# AdaptadorAcceso.net
KiCad netlist of a schematic drawn in EAGLE
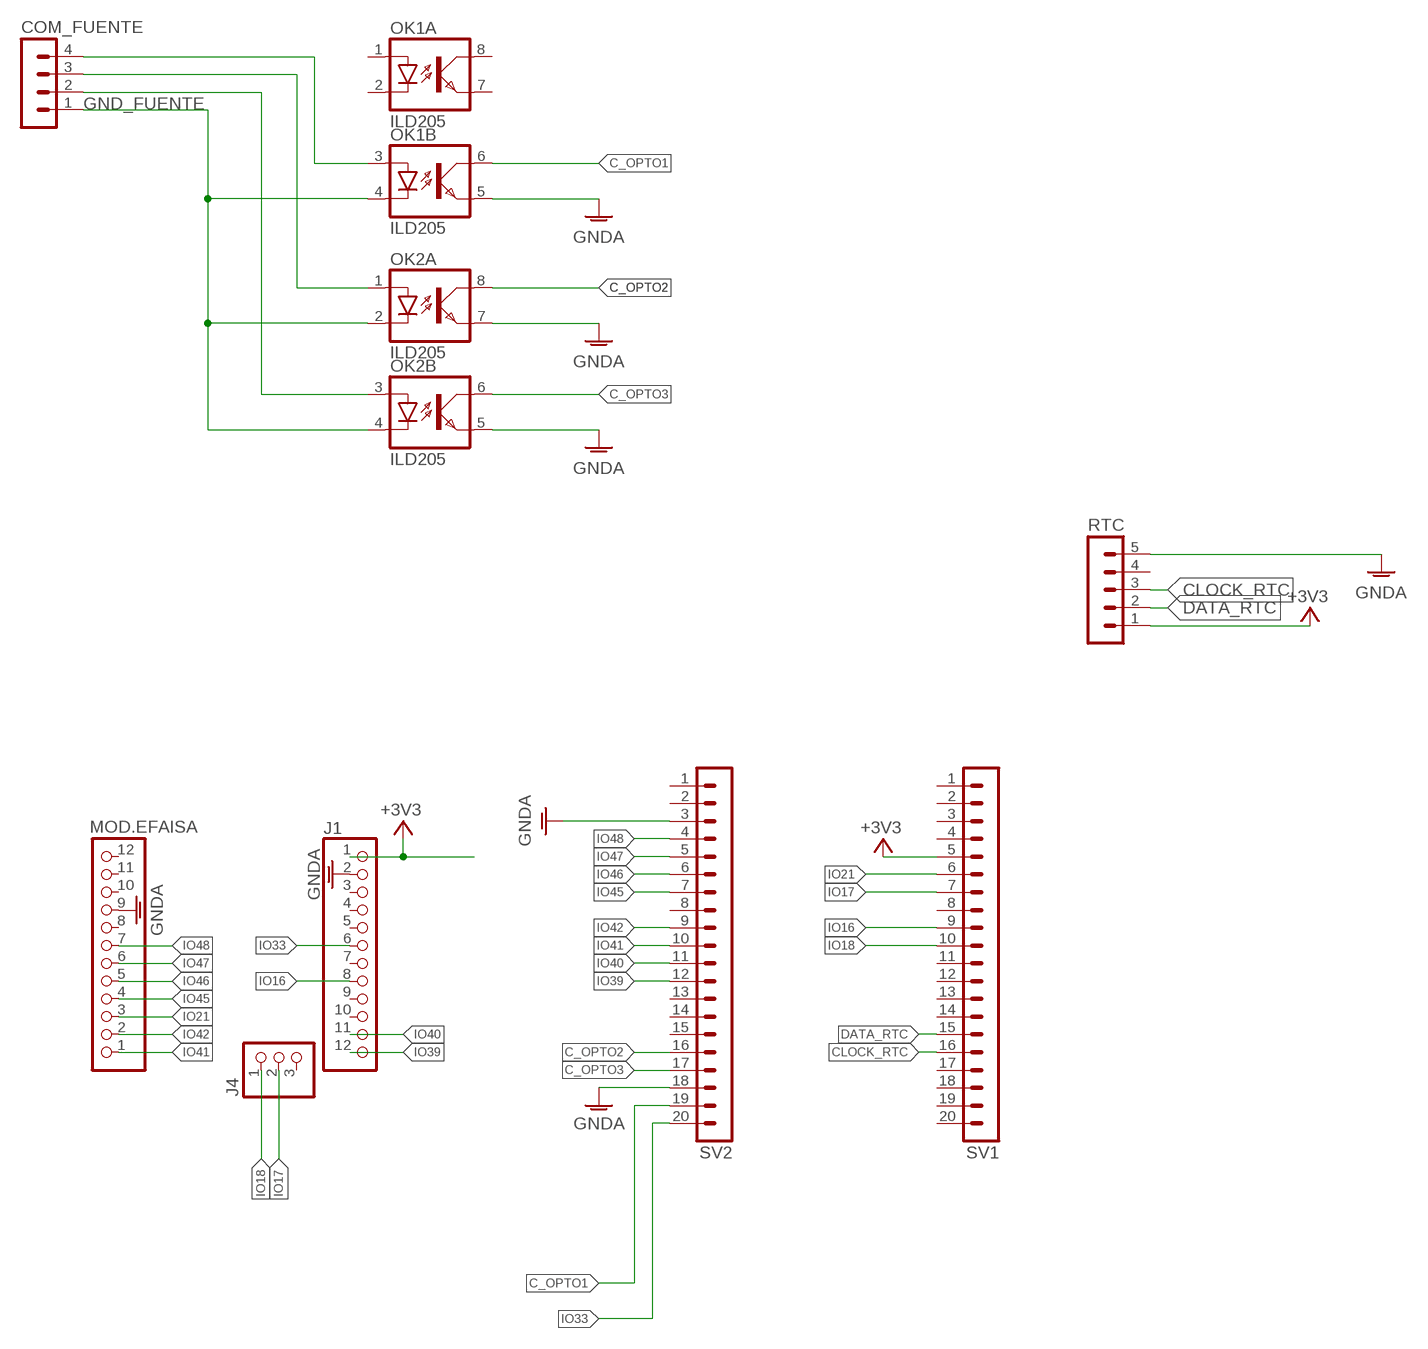
[diagram p0: schematic, sheet 1]

(export (version "E")
  (design (tool "Eeschema 10.0.6"))
  (components
    (comp (ref "COM_FUENTE")
      (value "MA04-1")
      (footprint "eagle-import:MA04-1")
      (libsource (lib "eagle-import") (part "MA04-1"))
    )
    (comp (ref "J1")
      (value "PINHD-1X12")
      (footprint "eagle-import:1X12")
      (libsource (lib "eagle-import") (part "PINHD-1X12"))
    )
    (comp (ref "J4")
      (value "PINHD-1X3")
      (footprint "eagle-import:1X03")
      (libsource (lib "eagle-import") (part "PINHD-1X3"))
    )
    (comp (ref "MOD.EFAISA")
      (value "PINHD-1X12")
      (footprint "eagle-import:1X12")
      (libsource (lib "eagle-import") (part "PINHD-1X12"))
    )
    (comp (ref "OK1")
      (value "ILD205")
      (footprint "eagle-import:SOIC08")
      (fields (field (name "MF") "VISHAY/TELEFUNKEN") (field (name "MPN") "ILD205T"))
      (libsource (lib "eagle-import") (part "ILD205"))
    )
    (comp (ref "OK2")
      (value "ILD205")
      (footprint "eagle-import:SOIC08")
      (fields (field (name "MF") "VISHAY/TELEFUNKEN") (field (name "MPN") "ILD205T"))
      (libsource (lib "eagle-import") (part "ILD205"))
    )
    (comp (ref "RTC")
      (value "MA05-1")
      (footprint "eagle-import:MA05-1")
      (libsource (lib "eagle-import") (part "MA05-1"))
    )
    (comp (ref "SV1")
      (value "MA20-1L")
      (footprint "eagle-import:MA20-1L")
      (libsource (lib "eagle-import") (part "MA20-1L"))
    )
    (comp (ref "SV2")
      (value "MA20-1L")
      (footprint "eagle-import:MA20-1L")
      (libsource (lib "eagle-import") (part "MA20-1L"))
    )
  )
  (nets
    (net (code "1") (name "+3V3") (class "Default")
      (node (ref "J1") (pin "1") (pinfunction "1_1") (pintype "passive"))
      (node (ref "RTC") (pin "1") (pinfunction "1_1") (pintype "passive"))
      (node (ref "SV1") (pin "5") (pinfunction "5_5") (pintype "passive"))
    )
    (net (code "2") (name "/GND_FUENTE") (class "Default")
      (node (ref "COM_FUENTE") (pin "1") (pinfunction "1_1") (pintype "passive"))
      (node (ref "OK1") (pin "4") (pinfunction "C_4") (pintype "passive"))
      (node (ref "OK2") (pin "2") (pinfunction "C_2") (pintype "passive"))
      (node (ref "OK2") (pin "4") (pinfunction "C_4") (pintype "passive"))
    )
    (net (code "3") (name "CLOCK_RTC") (class "Default")
      (node (ref "RTC") (pin "3") (pinfunction "3_3") (pintype "passive"))
      (node (ref "SV1") (pin "16") (pinfunction "16_16") (pintype "passive"))
    )
    (net (code "4") (name "C_OPTO1") (class "Default")
      (node (ref "OK1") (pin "6") (pinfunction "COL_6") (pintype "passive"))
      (node (ref "SV2") (pin "19") (pinfunction "19_19") (pintype "passive"))
    )
    (net (code "5") (name "C_OPTO2") (class "Default")
      (node (ref "OK2") (pin "8") (pinfunction "COL_8") (pintype "passive"))
      (node (ref "SV2") (pin "16") (pinfunction "16_16") (pintype "passive"))
    )
    (net (code "6") (name "C_OPTO3") (class "Default")
      (node (ref "OK2") (pin "6") (pinfunction "COL_6") (pintype "passive"))
      (node (ref "SV2") (pin "17") (pinfunction "17_17") (pintype "passive"))
    )
    (net (code "7") (name "DATA_RTC") (class "Default")
      (node (ref "RTC") (pin "2") (pinfunction "2_2") (pintype "passive"))
      (node (ref "SV1") (pin "15") (pinfunction "15_15") (pintype "passive"))
    )
    (net (code "8") (name "GNDA") (class "Default")
      (node (ref "J1") (pin "2") (pinfunction "2_2") (pintype "passive"))
      (node (ref "MOD.EFAISA") (pin "9") (pinfunction "9_9") (pintype "passive"))
      (node (ref "OK1") (pin "5") (pinfunction "EMIT_5") (pintype "passive"))
      (node (ref "OK2") (pin "5") (pinfunction "EMIT_5") (pintype "passive"))
      (node (ref "OK2") (pin "7") (pinfunction "EMIT_7") (pintype "passive"))
      (node (ref "RTC") (pin "5") (pinfunction "5_5") (pintype "passive"))
      (node (ref "SV2") (pin "18") (pinfunction "18_18") (pintype "passive"))
      (node (ref "SV2") (pin "3") (pinfunction "3_3") (pintype "passive"))
    )
    (net (code "9") (name "IO16") (class "Default")
      (node (ref "J1") (pin "8") (pinfunction "8_8") (pintype "passive"))
      (node (ref "SV1") (pin "9") (pinfunction "9_9") (pintype "passive"))
    )
    (net (code "10") (name "IO17") (class "Default")
      (node (ref "J4") (pin "2") (pinfunction "2_2") (pintype "passive"))
      (node (ref "SV1") (pin "7") (pinfunction "7_7") (pintype "passive"))
    )
    (net (code "11") (name "IO18") (class "Default")
      (node (ref "J4") (pin "1") (pinfunction "1_1") (pintype "passive"))
      (node (ref "SV1") (pin "10") (pinfunction "10_10") (pintype "passive"))
    )
    (net (code "12") (name "IO21") (class "Default")
      (node (ref "MOD.EFAISA") (pin "3") (pinfunction "3_3") (pintype "passive"))
      (node (ref "SV1") (pin "6") (pinfunction "6_6") (pintype "passive"))
    )
    (net (code "13") (name "IO33") (class "Default")
      (node (ref "J1") (pin "6") (pinfunction "6_6") (pintype "passive"))
      (node (ref "SV2") (pin "20") (pinfunction "20_20") (pintype "passive"))
    )
    (net (code "14") (name "IO39") (class "Default")
      (node (ref "J1") (pin "12") (pinfunction "12_12") (pintype "passive"))
      (node (ref "SV2") (pin "12") (pinfunction "12_12") (pintype "passive"))
    )
    (net (code "15") (name "IO40") (class "Default")
      (node (ref "J1") (pin "11") (pinfunction "11_11") (pintype "passive"))
      (node (ref "SV2") (pin "11") (pinfunction "11_11") (pintype "passive"))
    )
    (net (code "16") (name "IO41") (class "Default")
      (node (ref "MOD.EFAISA") (pin "1") (pinfunction "1_1") (pintype "passive"))
      (node (ref "SV2") (pin "10") (pinfunction "10_10") (pintype "passive"))
    )
    (net (code "17") (name "IO42") (class "Default")
      (node (ref "MOD.EFAISA") (pin "2") (pinfunction "2_2") (pintype "passive"))
      (node (ref "SV2") (pin "9") (pinfunction "9_9") (pintype "passive"))
    )
    (net (code "18") (name "IO45") (class "Default")
      (node (ref "MOD.EFAISA") (pin "4") (pinfunction "4_4") (pintype "passive"))
      (node (ref "SV2") (pin "7") (pinfunction "7_7") (pintype "passive"))
    )
    (net (code "19") (name "IO46") (class "Default")
      (node (ref "MOD.EFAISA") (pin "5") (pinfunction "5_5") (pintype "passive"))
      (node (ref "SV2") (pin "6") (pinfunction "6_6") (pintype "passive"))
    )
    (net (code "20") (name "IO47") (class "Default")
      (node (ref "MOD.EFAISA") (pin "6") (pinfunction "6_6") (pintype "passive"))
      (node (ref "SV2") (pin "5") (pinfunction "5_5") (pintype "passive"))
    )
    (net (code "21") (name "IO48") (class "Default")
      (node (ref "MOD.EFAISA") (pin "7") (pinfunction "7_7") (pintype "passive"))
      (node (ref "SV2") (pin "4") (pinfunction "4_4") (pintype "passive"))
    )
    (net (code "22") (name "Net-(OK1B-A)") (class "Default")
      (node (ref "COM_FUENTE") (pin "4") (pinfunction "4_4") (pintype "passive"))
      (node (ref "OK1") (pin "3") (pinfunction "A_3") (pintype "passive"))
    )
    (net (code "23") (name "Net-(OK2A-A)") (class "Default")
      (node (ref "COM_FUENTE") (pin "3") (pinfunction "3_3") (pintype "passive"))
      (node (ref "OK2") (pin "1") (pinfunction "A_1") (pintype "passive"))
    )
    (net (code "24") (name "Net-(OK2B-A)") (class "Default")
      (node (ref "COM_FUENTE") (pin "2") (pinfunction "2_2") (pintype "passive"))
      (node (ref "OK2") (pin "3") (pinfunction "A_3") (pintype "passive"))
    )
    (net (code "25") (name "unconnected-(J1-Pad3)") (class "Default")
      (node (ref "J1") (pin "3") (pinfunction "3_3") (pintype "passive"))
    )
    (net (code "26") (name "unconnected-(J1-Pad4)") (class "Default")
      (node (ref "J1") (pin "4") (pinfunction "4_4") (pintype "passive"))
    )
    (net (code "27") (name "unconnected-(J1-Pad5)") (class "Default")
      (node (ref "J1") (pin "5") (pinfunction "5_5") (pintype "passive"))
    )
    (net (code "28") (name "unconnected-(J1-Pad7)") (class "Default")
      (node (ref "J1") (pin "7") (pinfunction "7_7") (pintype "passive"))
    )
    (net (code "29") (name "unconnected-(J1-Pad9)") (class "Default")
      (node (ref "J1") (pin "9") (pinfunction "9_9") (pintype "passive"))
    )
    (net (code "30") (name "unconnected-(J1-Pad10)") (class "Default")
      (node (ref "J1") (pin "10") (pinfunction "10_10") (pintype "passive"))
    )
    (net (code "31") (name "unconnected-(J4-Pad3)") (class "Default")
      (node (ref "J4") (pin "3") (pinfunction "3_3") (pintype "passive"))
    )
    (net (code "32") (name "unconnected-(MOD.EFAISA-Pad8)") (class "Default")
      (node (ref "MOD.EFAISA") (pin "8") (pinfunction "8_8") (pintype "passive"))
    )
    (net (code "33") (name "unconnected-(MOD.EFAISA-Pad10)") (class "Default")
      (node (ref "MOD.EFAISA") (pin "10") (pinfunction "10_10") (pintype "passive"))
    )
    (net (code "34") (name "unconnected-(MOD.EFAISA-Pad11)") (class "Default")
      (node (ref "MOD.EFAISA") (pin "11") (pinfunction "11_11") (pintype "passive"))
    )
    (net (code "35") (name "unconnected-(MOD.EFAISA-Pad12)") (class "Default")
      (node (ref "MOD.EFAISA") (pin "12") (pinfunction "12_12") (pintype "passive"))
    )
    (net (code "36") (name "unconnected-(OK1A-A-Pad1)") (class "Default")
      (node (ref "OK1") (pin "1") (pinfunction "A_1") (pintype "passive"))
    )
    (net (code "37") (name "unconnected-(OK1A-C-Pad2)") (class "Default")
      (node (ref "OK1") (pin "2") (pinfunction "C_2") (pintype "passive"))
    )
    (net (code "38") (name "unconnected-(OK1A-COL-Pad8)") (class "Default")
      (node (ref "OK1") (pin "8") (pinfunction "COL_8") (pintype "passive"))
    )
    (net (code "39") (name "unconnected-(OK1A-EMIT-Pad7)") (class "Default")
      (node (ref "OK1") (pin "7") (pinfunction "EMIT_7") (pintype "passive"))
    )
    (net (code "40") (name "unconnected-(RTC-Pad4)") (class "Default")
      (node (ref "RTC") (pin "4") (pinfunction "4_4") (pintype "passive"))
    )
    (net (code "41") (name "unconnected-(SV1-Pad1)") (class "Default")
      (node (ref "SV1") (pin "1") (pinfunction "1_1") (pintype "passive"))
    )
    (net (code "42") (name "unconnected-(SV1-Pad2)") (class "Default")
      (node (ref "SV1") (pin "2") (pinfunction "2_2") (pintype "passive"))
    )
    (net (code "43") (name "unconnected-(SV1-Pad3)") (class "Default")
      (node (ref "SV1") (pin "3") (pinfunction "3_3") (pintype "passive"))
    )
    (net (code "44") (name "unconnected-(SV1-Pad4)") (class "Default")
      (node (ref "SV1") (pin "4") (pinfunction "4_4") (pintype "passive"))
    )
    (net (code "45") (name "unconnected-(SV1-Pad8)") (class "Default")
      (node (ref "SV1") (pin "8") (pinfunction "8_8") (pintype "passive"))
    )
    (net (code "46") (name "unconnected-(SV1-Pad11)") (class "Default")
      (node (ref "SV1") (pin "11") (pinfunction "11_11") (pintype "passive"))
    )
    (net (code "47") (name "unconnected-(SV1-Pad12)") (class "Default")
      (node (ref "SV1") (pin "12") (pinfunction "12_12") (pintype "passive"))
    )
    (net (code "48") (name "unconnected-(SV1-Pad13)") (class "Default")
      (node (ref "SV1") (pin "13") (pinfunction "13_13") (pintype "passive"))
    )
    (net (code "49") (name "unconnected-(SV1-Pad14)") (class "Default")
      (node (ref "SV1") (pin "14") (pinfunction "14_14") (pintype "passive"))
    )
    (net (code "50") (name "unconnected-(SV1-Pad17)") (class "Default")
      (node (ref "SV1") (pin "17") (pinfunction "17_17") (pintype "passive"))
    )
    (net (code "51") (name "unconnected-(SV1-Pad18)") (class "Default")
      (node (ref "SV1") (pin "18") (pinfunction "18_18") (pintype "passive"))
    )
    (net (code "52") (name "unconnected-(SV1-Pad19)") (class "Default")
      (node (ref "SV1") (pin "19") (pinfunction "19_19") (pintype "passive"))
    )
    (net (code "53") (name "unconnected-(SV1-Pad20)") (class "Default")
      (node (ref "SV1") (pin "20") (pinfunction "20_20") (pintype "passive"))
    )
    (net (code "54") (name "unconnected-(SV2-Pad1)") (class "Default")
      (node (ref "SV2") (pin "1") (pinfunction "1_1") (pintype "passive"))
    )
    (net (code "55") (name "unconnected-(SV2-Pad2)") (class "Default")
      (node (ref "SV2") (pin "2") (pinfunction "2_2") (pintype "passive"))
    )
    (net (code "56") (name "unconnected-(SV2-Pad8)") (class "Default")
      (node (ref "SV2") (pin "8") (pinfunction "8_8") (pintype "passive"))
    )
    (net (code "57") (name "unconnected-(SV2-Pad13)") (class "Default")
      (node (ref "SV2") (pin "13") (pinfunction "13_13") (pintype "passive"))
    )
    (net (code "58") (name "unconnected-(SV2-Pad14)") (class "Default")
      (node (ref "SV2") (pin "14") (pinfunction "14_14") (pintype "passive"))
    )
    (net (code "59") (name "unconnected-(SV2-Pad15)") (class "Default")
      (node (ref "SV2") (pin "15") (pinfunction "15_15") (pintype "passive"))
    )
  )
)
